# XC7A35TFTG256_bank35.net
KiCad netlist of a schematic drawn in Altium Designer
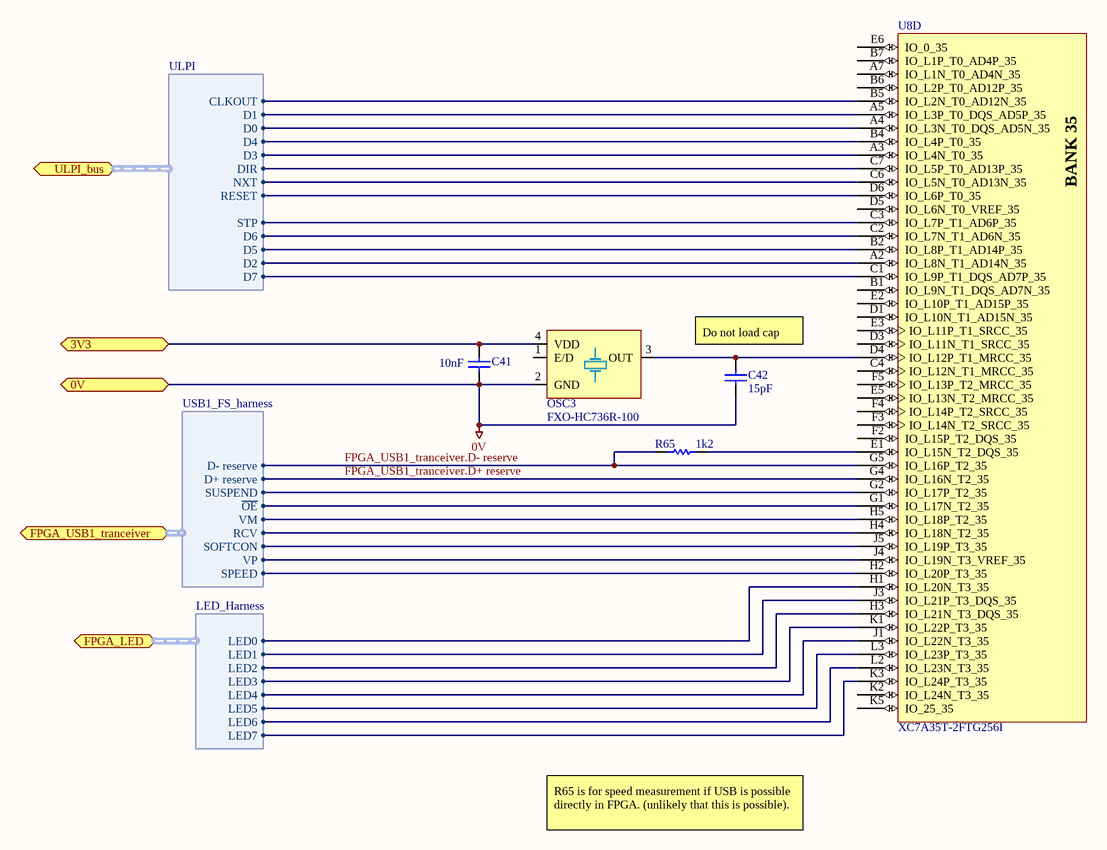
[diagram p0: XC7A35TFTG256_bank35.SchDoc]

(export (version "E")
  (design (tool "Eeschema 10.0.6"))
  (components
    (comp (ref "C41")
      (value "10nF")
      (footprint "CAPC0603(1608)100_L")
      (description "CAP 10nF 16V ±1% 0603 (1608 Metric) Thickness 1mm SMD")
      (fields (field (name "TOLERANCE") "Â±1%") (field (name "Comment") "CAP 10nF 16V 0603(1608)"))
      (libsource (lib "Altium Content Vault") (part "CMP-1035-02309-1"))
    )
    (comp (ref "C42")
      (value "15pF")
      (footprint "CAPC0603(1608)100_N")
      (description "CAP 15pF 16V ±0.25pF 0603 (1608 Metric) Thickness 1mm SMD")
      (fields (field (name "TOLERANCE") "Â±0.25pF") (field (name "Comment") "CAP 15pF 16V 0603(1608)"))
      (libsource (lib "Altium Content Vault") (part "CMP-1035-00665-1"))
    )
    (comp (ref "OSC3")
      (value "FXO-HC736R-100")
      (footprint "FXO-HC73")
      (libsource (lib "dmpro16lib") (part "FXO-HC736R-100"))
    )
    (comp (ref "R65")
      (value "1k2")
      (footprint "RESC0603(1608)_M")
      (description "1K2 0.1W 1% 0603 (1608 Metric)  SMD")
      (fields (field (name "POWER") "0.1 W") (field (name "TOLERANCE") "1 %"))
      (libsource (lib "Altium Content Vault") (part "CMP-1012-00518-1"))
    )
    (comp (ref "U8")
      (value "XC7A35T-2FTG256I")
      (footprint "FTG256")
      (description "Artix-7 FPGA, 170 User I/Os, 0 GTP, 256-Ball BGA, Speed Grade 2, Industrial Grade, Pb-Free")
      (fields (field (name "MANUFACTURER") "Xilinx"))
      (libsource (lib "Altium Content Vault") (part "XLNX-XC7A35T-FTG256"))
    )
  )
  (nets
    (net (code "4") (name "/3V3") (class "Default")
      (node (ref "C41") (pin "2") (pinfunction "2_2") (pintype "passive"))
      (node (ref "OSC3") (pin "4") (pinfunction "VDD_4") (pintype "passive"))
    )
    (net (code "5") (name "/CLKOUT") (class "Default")
      (node (ref "U8") (pin "B5") (pinfunction "IO_L2N_T0_AD12N_35_B5") (pintype "bidirectional"))
    )
    (net (code "6") (name "/D0") (class "Default")
      (node (ref "U8") (pin "A4") (pinfunction "IO_L3N_T0_DQS_AD5N_35_A4") (pintype "bidirectional"))
    )
    (net (code "7") (name "/D1") (class "Default")
      (node (ref "U8") (pin "A5") (pinfunction "IO_L3P_T0_DQS_AD5P_35_A5") (pintype "bidirectional"))
    )
    (net (code "8") (name "/D2") (class "Default")
      (node (ref "U8") (pin "A2") (pinfunction "IO_L8N_T1_AD14N_35_A2") (pintype "bidirectional"))
    )
    (net (code "9") (name "/D3") (class "Default")
      (node (ref "U8") (pin "A3") (pinfunction "IO_L4N_T0_35_A3") (pintype "bidirectional"))
    )
    (net (code "10") (name "/D4") (class "Default")
      (node (ref "U8") (pin "B4") (pinfunction "IO_L4P_T0_35_B4") (pintype "bidirectional"))
    )
    (net (code "11") (name "/D5") (class "Default")
      (node (ref "U8") (pin "B2") (pinfunction "IO_L8P_T1_AD14P_35_B2") (pintype "bidirectional"))
    )
    (net (code "12") (name "/D6") (class "Default")
      (node (ref "U8") (pin "C2") (pinfunction "IO_L7N_T1_AD6N_35_C2") (pintype "bidirectional"))
    )
    (net (code "13") (name "/D7") (class "Default")
      (node (ref "U8") (pin "C1") (pinfunction "IO_L9P_T1_DQS_AD7P_35_C1") (pintype "bidirectional"))
    )
    (net (code "14") (name "/DIR") (class "Default")
      (node (ref "U8") (pin "C7") (pinfunction "IO_L5P_T0_AD13P_35_C7") (pintype "bidirectional"))
    )
    (net (code "15") (name "/FPGA_USB1_tranceiver.D+ reserve") (class "Default")
      (node (ref "U8") (pin "G4") (pinfunction "IO_L16N_T2_35_G4") (pintype "bidirectional"))
    )
    (net (code "16") (name "/FPGA_USB1_tranceiver.D- reserve") (class "Default")
      (node (ref "R65") (pin "1") (pinfunction "1_1") (pintype "passive"))
      (node (ref "U8") (pin "G5") (pinfunction "IO_L16P_T2_35_G5") (pintype "bidirectional"))
    )
    (net (code "17") (name "/LED0") (class "Default")
      (node (ref "U8") (pin "H1") (pinfunction "IO_L20N_T3_35_H1") (pintype "bidirectional"))
    )
    (net (code "18") (name "/LED1") (class "Default")
      (node (ref "U8") (pin "J3") (pinfunction "IO_L21P_T3_DQS_35_J3") (pintype "bidirectional"))
    )
    (net (code "19") (name "/LED2") (class "Default")
      (node (ref "U8") (pin "H3") (pinfunction "IO_L21N_T3_DQS_35_H3") (pintype "bidirectional"))
    )
    (net (code "20") (name "/LED3") (class "Default")
      (node (ref "U8") (pin "K1") (pinfunction "IO_L22P_T3_35_K1") (pintype "bidirectional"))
    )
    (net (code "21") (name "/LED4") (class "Default")
      (node (ref "U8") (pin "J1") (pinfunction "IO_L22N_T3_35_J1") (pintype "bidirectional"))
    )
    (net (code "22") (name "/LED5") (class "Default")
      (node (ref "U8") (pin "L3") (pinfunction "IO_L23P_T3_35_L3") (pintype "bidirectional"))
    )
    (net (code "23") (name "/LED6") (class "Default")
      (node (ref "U8") (pin "L2") (pinfunction "IO_L23N_T3_35_L2") (pintype "bidirectional"))
    )
    (net (code "24") (name "/LED7") (class "Default")
      (node (ref "U8") (pin "K3") (pinfunction "IO_L24P_T3_35_K3") (pintype "bidirectional"))
    )
    (net (code "25") (name "/NXT") (class "Default")
      (node (ref "U8") (pin "C6") (pinfunction "IO_L5N_T0_AD13N_35_C6") (pintype "bidirectional"))
    )
    (net (code "26") (name "/RCV") (class "Default")
      (node (ref "U8") (pin "H4") (pinfunction "IO_L18N_T2_35_H4") (pintype "bidirectional"))
    )
    (net (code "27") (name "/RESET") (class "Default")
      (node (ref "U8") (pin "D6") (pinfunction "IO_L6P_T0_35_D6") (pintype "bidirectional"))
    )
    (net (code "28") (name "/SOFTCON") (class "Default")
      (node (ref "U8") (pin "J5") (pinfunction "IO_L19P_T3_35_J5") (pintype "bidirectional"))
    )
    (net (code "29") (name "/SPEED") (class "Default")
      (node (ref "U8") (pin "H2") (pinfunction "IO_L20P_T3_35_H2") (pintype "bidirectional"))
    )
    (net (code "30") (name "/STP") (class "Default")
      (node (ref "U8") (pin "C3") (pinfunction "IO_L7P_T1_AD6P_35_C3") (pintype "bidirectional"))
    )
    (net (code "31") (name "/SUSPEND") (class "Default")
      (node (ref "U8") (pin "G2") (pinfunction "IO_L17P_T2_35_G2") (pintype "bidirectional"))
    )
    (net (code "32") (name "/VM") (class "Default")
      (node (ref "U8") (pin "H5") (pinfunction "IO_L18P_T2_35_H5") (pintype "bidirectional"))
    )
    (net (code "33") (name "/VP") (class "Default")
      (node (ref "U8") (pin "J4") (pinfunction "IO_L19N_T3_VREF_35_J4") (pintype "bidirectional"))
    )
    (net (code "37") (name "/~{OE}") (class "Default")
      (node (ref "U8") (pin "G1") (pinfunction "IO_L17N_T2_35_G1") (pintype "bidirectional"))
    )
    (net (code "38") (name "0V") (class "Default")
      (node (ref "C41") (pin "1") (pinfunction "1_1") (pintype "passive"))
      (node (ref "C42") (pin "1") (pinfunction "1_1") (pintype "passive"))
      (node (ref "OSC3") (pin "2") (pinfunction "GND_2") (pintype "passive"))
    )
    (net (code "39") (name "Net-(OSC3-OUT)") (class "Default")
      (node (ref "C42") (pin "2") (pinfunction "2_2") (pintype "passive"))
      (node (ref "OSC3") (pin "3") (pinfunction "OUT_3") (pintype "passive"))
      (node (ref "U8") (pin "D4") (pinfunction "IO_L12P_T1_MRCC_35_D4") (pintype "bidirectional"))
    )
    (net (code "40") (name "Net-(U8D-IO_L15N_T2_DQS_35)") (class "Default")
      (node (ref "R65") (pin "2") (pinfunction "2_2") (pintype "passive"))
      (node (ref "U8") (pin "E1") (pinfunction "IO_L15N_T2_DQS_35_E1") (pintype "bidirectional"))
    )
    (net (code "41") (name "unconnected-(OSC3-E{slash}D-Pad1)") (class "Default")
      (node (ref "OSC3") (pin "1") (pinfunction "E/D_1") (pintype "passive"))
    )
    (net (code "42") (name "unconnected-(U8D-IO_0_35-PadE6)") (class "Default")
      (node (ref "U8") (pin "E6") (pinfunction "IO_0_35_E6") (pintype "bidirectional"))
    )
    (net (code "43") (name "unconnected-(U8D-IO_25_35-PadK5)") (class "Default")
      (node (ref "U8") (pin "K5") (pinfunction "IO_25_35_K5") (pintype "bidirectional"))
    )
    (net (code "44") (name "unconnected-(U8D-IO_L1N_T0_AD4N_35-PadA7)") (class "Default")
      (node (ref "U8") (pin "A7") (pinfunction "IO_L1N_T0_AD4N_35_A7") (pintype "bidirectional"))
    )
    (net (code "45") (name "unconnected-(U8D-IO_L1P_T0_AD4P_35-PadB7)") (class "Default")
      (node (ref "U8") (pin "B7") (pinfunction "IO_L1P_T0_AD4P_35_B7") (pintype "bidirectional"))
    )
    (net (code "46") (name "unconnected-(U8D-IO_L2P_T0_AD12P_35-PadB6)") (class "Default")
      (node (ref "U8") (pin "B6") (pinfunction "IO_L2P_T0_AD12P_35_B6") (pintype "bidirectional"))
    )
    (net (code "47") (name "unconnected-(U8D-IO_L6N_T0_VREF_35-PadD5)") (class "Default")
      (node (ref "U8") (pin "D5") (pinfunction "IO_L6N_T0_VREF_35_D5") (pintype "bidirectional"))
    )
    (net (code "48") (name "unconnected-(U8D-IO_L9N_T1_DQS_AD7N_35-PadB1)") (class "Default")
      (node (ref "U8") (pin "B1") (pinfunction "IO_L9N_T1_DQS_AD7N_35_B1") (pintype "bidirectional"))
    )
    (net (code "49") (name "unconnected-(U8D-IO_L10N_T1_AD15N_35-PadD1)") (class "Default")
      (node (ref "U8") (pin "D1") (pinfunction "IO_L10N_T1_AD15N_35_D1") (pintype "bidirectional"))
    )
    (net (code "50") (name "unconnected-(U8D-IO_L10P_T1_AD15P_35-PadE2)") (class "Default")
      (node (ref "U8") (pin "E2") (pinfunction "IO_L10P_T1_AD15P_35_E2") (pintype "bidirectional"))
    )
    (net (code "51") (name "unconnected-(U8D-IO_L11N_T1_SRCC_35-PadD3)") (class "Default")
      (node (ref "U8") (pin "D3") (pinfunction "IO_L11N_T1_SRCC_35_D3") (pintype "bidirectional"))
    )
    (net (code "52") (name "unconnected-(U8D-IO_L11P_T1_SRCC_35-PadE3)") (class "Default")
      (node (ref "U8") (pin "E3") (pinfunction "IO_L11P_T1_SRCC_35_E3") (pintype "bidirectional"))
    )
    (net (code "53") (name "unconnected-(U8D-IO_L12N_T1_MRCC_35-PadC4)") (class "Default")
      (node (ref "U8") (pin "C4") (pinfunction "IO_L12N_T1_MRCC_35_C4") (pintype "bidirectional"))
    )
    (net (code "54") (name "unconnected-(U8D-IO_L13N_T2_MRCC_35-PadE5)") (class "Default")
      (node (ref "U8") (pin "E5") (pinfunction "IO_L13N_T2_MRCC_35_E5") (pintype "bidirectional"))
    )
    (net (code "55") (name "unconnected-(U8D-IO_L13P_T2_MRCC_35-PadF5)") (class "Default")
      (node (ref "U8") (pin "F5") (pinfunction "IO_L13P_T2_MRCC_35_F5") (pintype "bidirectional"))
    )
    (net (code "56") (name "unconnected-(U8D-IO_L14N_T2_SRCC_35-PadF3)") (class "Default")
      (node (ref "U8") (pin "F3") (pinfunction "IO_L14N_T2_SRCC_35_F3") (pintype "bidirectional"))
    )
    (net (code "57") (name "unconnected-(U8D-IO_L14P_T2_SRCC_35-PadF4)") (class "Default")
      (node (ref "U8") (pin "F4") (pinfunction "IO_L14P_T2_SRCC_35_F4") (pintype "bidirectional"))
    )
    (net (code "58") (name "unconnected-(U8D-IO_L15P_T2_DQS_35-PadF2)") (class "Default")
      (node (ref "U8") (pin "F2") (pinfunction "IO_L15P_T2_DQS_35_F2") (pintype "bidirectional"))
    )
    (net (code "59") (name "unconnected-(U8D-IO_L24N_T3_35-PadK2)") (class "Default")
      (node (ref "U8") (pin "K2") (pinfunction "IO_L24N_T3_35_K2") (pintype "bidirectional"))
    )
  )
)
